# Fuente3V.net
KiCad netlist of a schematic drawn in Altium Designer
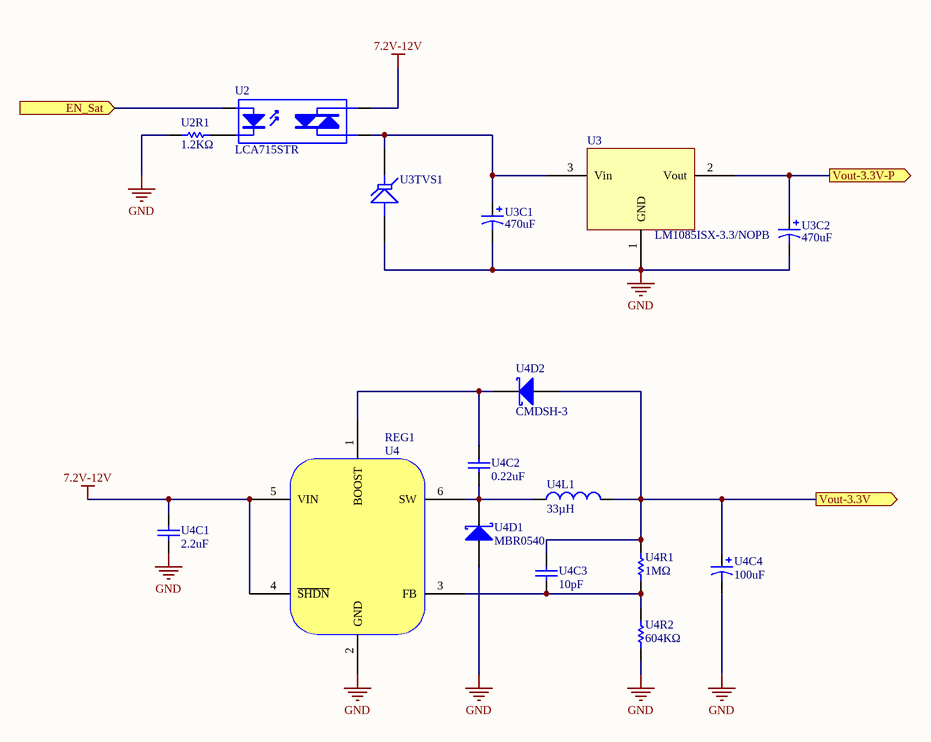
[diagram p0: Fuente3V.SchDoc]

(export (version "E")
  (design (tool "Eeschema 10.0.6"))
  (components
    (comp (ref "U2")
      (value "LCA715STR")
      (footprint "SOP-6")
      (description "RELAY OPTOMOS 1.8A SPST-NO 6-SMD")
      (fields (field (name "MANUFACTURER") "IXYS Integrated Circuits Division"))
      (libsource (lib "Miscellaneous Devices") (part "Opto TRIAC"))
    )
    (comp (ref "U2R1")
      (value "1.2KΩ")
      (footprint "0805-RES")
      (description "RES SMD 1.2K OHM 1% 1/8W 0805")
      (fields
        (field (name "MANUFACTURER") "Panasonic Electronic Components")
        (field (name "MANUFACTURER PART NUMBER") "ERJ-6ENF1201V")
      )
      (libsource (lib "Miscellaneous Devices") (part "Res1"))
    )
    (comp (ref "U3")
      (value "LM1085ISX-3.3/NOPB")
      (footprint "D2PAK3-TO263")
      (description "Linear Voltage Regulator IC Positive Fixed 1 Output 3.3V 3A DDPAK/TO-263-3")
      (fields (field (name "MANUFACTURER") "Texas Instruments"))
      (libsource (lib "*") (part "LD1117A"))
    )
    (comp (ref "U3C1")
      (value "470uF")
      (footprint "CAP-12.5X20X5")
      (description "470µF 50V Aluminum Capacitors Radial, Can 27 mOhm @ 100kHz 5000 Hrs @ 105°C")
      (fields
        (field (name "MANUFACTURER") "Kemet")
        (field (name "MANUFACTURER PART NUMBER") "ESY477M050AL3AA")
      )
      (libsource (lib "Miscellaneous Devices") (part "Cap Pol1"))
    )
    (comp (ref "U3C2")
      (value "470uF")
      (footprint "CAP-12.5X20X5")
      (description "470µF 50V Aluminum Capacitors Radial, Can 27 mOhm @ 100kHz 5000 Hrs @ 105°C")
      (fields
        (field (name "MANUFACTURER") "Kemet")
        (field (name "MANUFACTURER PART NUMBER") "ESY477M050AL3AA")
      )
      (libsource (lib "Miscellaneous Devices") (part "Cap Pol1"))
    )
    (comp (ref "U3TVS1")
      (value "20V")
      (footprint "DO-219AB")
      (description "TVS DIODE 18V 29.2V SMF")
      (fields
        (field (name "MANUFACTURER") "Vishay Semiconductor Diodes Division")
        (field (name "MANUFACTURER PART NUMBER") "SMF18A-E3-08")
      )
      (libsource (lib "Miscellaneous Devices") (part "Tranzorb"))
    )
    (comp (ref "U4")
      (value "REG1")
      (footprint "SOT23-6")
      (description "LINEAR TECHNOLOGY  LT1934  IC REG BUCK ADJ 0.3A SOT23-6")
      (fields
        (field (name "MANUFACTURER PART NUMBER") "LT1934")
        (field (name "MANUFACTURER") "Linear Technology/Analog Devices")
      )
      (libsource (lib "LibreriaEstandar2") (part "LT1934"))
    )
    (comp (ref "U4C1")
      (value "2.2uF")
      (footprint "1206-cap")
      (description "CAP CER 2.2UF 50V 10% X5R 1206")
      (fields
        (field (name "MANUFACTURER") "Taiyo Yuden")
        (field (name "MANUFACTURER PART NUMBER") "UMK316BJ225KD-T")
      )
      (libsource (lib "LibreriaEstandar2") (part "Cap"))
    )
    (comp (ref "U4C2")
      (value "0.22uF")
      (footprint "1206-CAP")
      (description "CAP CER 0.22UF 50V 10% X7R 1206")
      (fields
        (field (name "MANUFACTURER") "Samsung Electro-mechanics")
        (field (name "MANUFACTURER PART NUMBER") "CL31B224KBFNNNE")
      )
      (libsource (lib "LibreriaEstandar2") (part "Cap"))
    )
    (comp (ref "U4C3")
      (value "10pF")
      (footprint "1206-CAP")
      (description "CAP CER 10PF 50V 10% NP0 1206")
      (fields
        (field (name "MANUFACTURER") "Kemet")
        (field (name "MANUFACTURER PART NUMBER") "C1206C100K5GACTU")
      )
      (libsource (lib "LibreriaEstandar2") (part "Cap"))
    )
    (comp (ref "U4C4")
      (value "100uF")
      (footprint "7343-31")
      (description "CAP TANT 100UF 16V 10% 2917")
      (fields
        (field (name "MANUFACTURER") "Kemet")
        (field (name "MANUFACTURER PART NUMBER") "T495D107K016AHE125")
      )
      (libsource (lib "Miscellaneous Devices") (part "Cap Pol1"))
    )
    (comp (ref "U4D1")
      (value "MBR0540")
      (footprint "SOD-123")
      (description "DIODE SCHOTTKY 40V 500MA SOD123")
      (fields
        (field (name "MANUFACTURER") "Micro Commercial Co")
        (field (name "MANUFACTURER PART NUMBER") "MBR0540-TP")
      )
      (libsource (lib "Miscellaneous Devices") (part "D Schottky"))
    )
    (comp (ref "U4D2")
      (value "CMDSH-3")
      (footprint "SOD-323")
      (description "DIODE SCHOTTKY 30V 100MA SOD323")
      (fields
        (field (name "MANUFACTURER") "Central Semiconductor Corp")
        (field (name "MANUFACTURER PART NUMBER") "CMDSH-3 TR")
      )
      (libsource (lib "Miscellaneous Devices") (part "D Schottky"))
    )
    (comp (ref "U4L1")
      (value "33µH")
      (footprint "784774033")
      (description "WE-PD2A SMD Power Inductor")
      (fields
        (field (name "MANUFACTURER") "Wurth Elektronik")
        (field (name "MANUFACTURER PART NUMBER") "784774133")
      )
      (libsource (lib "Miscellaneous Devices") (part "Inductor"))
    )
    (comp (ref "U4R1")
      (value "1MΩ")
      (footprint "0805-RES")
      (description "RES SMD 1M OHM 0.1% 1/8W 0805")
      (fields
        (field (name "MANUFACTURER") "Panasonic Electronic Components")
        (field (name "MANUFACTURER PART NUMBER") "ERA-6AEB105V")
      )
      (libsource (lib "LibreriaEstandar2") (part "Res1"))
    )
    (comp (ref "U4R2")
      (value "604KΩ")
      (footprint "0805-RES")
      (description "RES SMD 604K OHM 0.1% 1/8W 0805")
      (fields
        (field (name "MANUFACTURER") "Yageo")
        (field (name "MANUFACTURER PART NUMBER") "RT0805BRD07604KL")
      )
      (libsource (lib "LibreriaEstandar2") (part "Res1"))
    )
  )
  (nets
    (net (code "1") (name "/EN_Sat") (class "Default")
      (node (ref "U2") (pin "1") (pinfunction "A_1") (pintype "passive"))
    )
    (net (code "2") (name "/Vout-3.3V") (class "Default")
      (node (ref "U4C3") (pin "2") (pinfunction "2_2") (pintype "passive"))
      (node (ref "U4C4") (pin "1") (pinfunction "1_1") (pintype "passive"))
      (node (ref "U4D2") (pin "1") (pinfunction "A_1") (pintype "passive"))
      (node (ref "U4L1") (pin "2") (pinfunction "2_2") (pintype "passive"))
      (node (ref "U4R1") (pin "2") (pinfunction "2_2") (pintype "passive"))
    )
    (net (code "3") (name "/Vout-3.3V-P") (class "Default")
      (node (ref "U3") (pin "2") (pinfunction "Vout_2") (pintype "passive"))
      (node (ref "U3C2") (pin "1") (pinfunction "1_1") (pintype "passive"))
    )
    (net (code "4") (name "7.2V-12V") (class "Default")
      (node (ref "U2") (pin "6") (pinfunction "A/K_6") (pintype "passive"))
      (node (ref "U4") (pin "4") (pinfunction "~{SHDN}_4") (pintype "passive"))
      (node (ref "U4") (pin "5") (pinfunction "VIN_5") (pintype "passive"))
      (node (ref "U4C1") (pin "2") (pinfunction "2_2") (pintype "passive"))
    )
    (net (code "5") (name "GND") (class "Default")
      (node (ref "U2R1") (pin "1") (pinfunction "1_1") (pintype "passive"))
      (node (ref "U3") (pin "1") (pinfunction "GND_1") (pintype "passive"))
      (node (ref "U3C1") (pin "2") (pinfunction "2_2") (pintype "passive"))
      (node (ref "U3C2") (pin "2") (pinfunction "2_2") (pintype "passive"))
      (node (ref "U3TVS1") (pin "1") (pinfunction "A_1") (pintype "passive"))
      (node (ref "U4") (pin "2") (pinfunction "GND_2") (pintype "passive"))
      (node (ref "U4C1") (pin "1") (pinfunction "1_1") (pintype "passive"))
      (node (ref "U4C4") (pin "2") (pinfunction "2_2") (pintype "passive"))
      (node (ref "U4D1") (pin "1") (pinfunction "A_1") (pintype "passive"))
      (node (ref "U4R2") (pin "1") (pinfunction "1_1") (pintype "passive"))
    )
    (net (code "6") (name "Net-(U2-K)") (class "Default")
      (node (ref "U2") (pin "2") (pinfunction "K_2") (pintype "passive"))
      (node (ref "U2R1") (pin "2") (pinfunction "2_2") (pintype "passive"))
    )
    (net (code "7") (name "Net-(U3-Vin)") (class "Default")
      (node (ref "U2") (pin "4") (pinfunction "A/K_4") (pintype "passive"))
      (node (ref "U3") (pin "3") (pinfunction "Vin_3") (pintype "passive"))
      (node (ref "U3C1") (pin "1") (pinfunction "1_1") (pintype "passive"))
      (node (ref "U3TVS1") (pin "2") (pinfunction "K_2") (pintype "passive"))
    )
    (net (code "8") (name "Net-(U4-BOOST)") (class "Default")
      (node (ref "U4") (pin "1") (pinfunction "BOOST_1") (pintype "passive"))
      (node (ref "U4C2") (pin "2") (pinfunction "2_2") (pintype "passive"))
      (node (ref "U4D2") (pin "2") (pinfunction "K_2") (pintype "passive"))
    )
    (net (code "9") (name "Net-(U4-FB)") (class "Default")
      (node (ref "U4") (pin "3") (pinfunction "FB_3") (pintype "passive"))
      (node (ref "U4C3") (pin "1") (pinfunction "1_1") (pintype "passive"))
      (node (ref "U4R1") (pin "1") (pinfunction "1_1") (pintype "passive"))
      (node (ref "U4R2") (pin "2") (pinfunction "2_2") (pintype "passive"))
    )
    (net (code "10") (name "Net-(U4-SW)") (class "Default")
      (node (ref "U4") (pin "6") (pinfunction "SW_6") (pintype "passive"))
      (node (ref "U4C2") (pin "1") (pinfunction "1_1") (pintype "passive"))
      (node (ref "U4D1") (pin "2") (pinfunction "K_2") (pintype "passive"))
      (node (ref "U4L1") (pin "1") (pinfunction "1_1") (pintype "passive"))
    )
  )
)
